# Superseal.net
KiCad netlist of a schematic drawn in Altium Designer
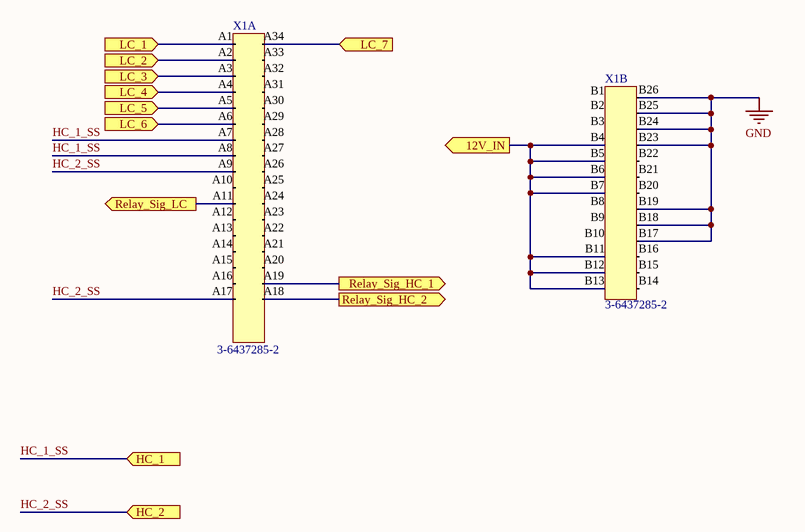
[diagram p0: Superseal.SchDoc]

(export (version "E")
  (design (tool "Eeschema 10.0.6"))
  (components
    (comp (ref "X1")
      (value "3-6437285-2")
      (footprint "SUPERSEAL 60POS 90Deg")
      (description "90 Degree")
      (libsource (lib "Altium-Lib") (part "CONN Superseal 60POS"))
    )
  )
  (nets
    (net (code "1") (name "/12V_IN") (class "Default")
      (node (ref "X1") (pin "B11") (pintype "bidirectional"))
      (node (ref "X1") (pin "B12") (pintype "bidirectional"))
      (node (ref "X1") (pin "B13") (pintype "bidirectional"))
      (node (ref "X1") (pin "B4") (pintype "bidirectional"))
      (node (ref "X1") (pin "B5") (pintype "bidirectional"))
      (node (ref "X1") (pin "B6") (pintype "bidirectional"))
      (node (ref "X1") (pin "B7") (pintype "bidirectional"))
    )
    (net (code "2") (name "/HC_1_SS") (class "Default")
      (node (ref "X1") (pin "A7") (pintype "bidirectional"))
      (node (ref "X1") (pin "A8") (pintype "bidirectional"))
    )
    (net (code "3") (name "/HC_2_SS") (class "Default")
      (node (ref "X1") (pin "A17") (pintype "bidirectional"))
      (node (ref "X1") (pin "A9") (pintype "bidirectional"))
    )
    (net (code "4") (name "/LC_1") (class "Default") (node (ref "X1") (pin "A1") (pintype "bidirectional")))
    (net (code "5") (name "/LC_2") (class "Default") (node (ref "X1") (pin "A2") (pintype "bidirectional")))
    (net (code "6") (name "/LC_3") (class "Default") (node (ref "X1") (pin "A3") (pintype "bidirectional")))
    (net (code "7") (name "/LC_4") (class "Default") (node (ref "X1") (pin "A4") (pintype "bidirectional")))
    (net (code "8") (name "/LC_5") (class "Default") (node (ref "X1") (pin "A5") (pintype "bidirectional")))
    (net (code "9") (name "/LC_6") (class "Default") (node (ref "X1") (pin "A6") (pintype "bidirectional")))
    (net (code "10") (name "/LC_7") (class "Default") (node (ref "X1") (pin "A34") (pintype "bidirectional")))
    (net (code "11") (name "/Relay_Sig_HC_1") (class "Default")
      (node (ref "X1") (pin "A19") (pintype "bidirectional"))
    )
    (net (code "12") (name "/Relay_Sig_HC_2") (class "Default")
      (node (ref "X1") (pin "A18") (pintype "bidirectional"))
    )
    (net (code "13") (name "/Relay_Sig_LC") (class "Default")
      (node (ref "X1") (pin "A11") (pintype "bidirectional"))
    )
    (net (code "14") (name "GND") (class "Default")
      (node (ref "X1") (pin "B17") (pintype "bidirectional"))
      (node (ref "X1") (pin "B18") (pintype "bidirectional"))
      (node (ref "X1") (pin "B19") (pintype "bidirectional"))
      (node (ref "X1") (pin "B23") (pintype "bidirectional"))
      (node (ref "X1") (pin "B24") (pintype "bidirectional"))
      (node (ref "X1") (pin "B25") (pintype "bidirectional"))
      (node (ref "X1") (pin "B26") (pintype "bidirectional"))
    )
    (net (code "15") (name "unconnected-(X1-PadA10)") (class "Default")
      (node (ref "X1") (pin "A10") (pintype "bidirectional"))
    )
    (net (code "16") (name "unconnected-(X1-PadA12)") (class "Default")
      (node (ref "X1") (pin "A12") (pintype "bidirectional"))
    )
    (net (code "17") (name "unconnected-(X1-PadA13)") (class "Default")
      (node (ref "X1") (pin "A13") (pintype "bidirectional"))
    )
    (net (code "18") (name "unconnected-(X1-PadA14)") (class "Default")
      (node (ref "X1") (pin "A14") (pintype "bidirectional"))
    )
    (net (code "19") (name "unconnected-(X1-PadA15)") (class "Default")
      (node (ref "X1") (pin "A15") (pintype "bidirectional"))
    )
    (net (code "20") (name "unconnected-(X1-PadA16)") (class "Default")
      (node (ref "X1") (pin "A16") (pintype "bidirectional"))
    )
    (net (code "21") (name "unconnected-(X1-PadA20)") (class "Default")
      (node (ref "X1") (pin "A20") (pintype "bidirectional"))
    )
    (net (code "22") (name "unconnected-(X1-PadA21)") (class "Default")
      (node (ref "X1") (pin "A21") (pintype "bidirectional"))
    )
    (net (code "23") (name "unconnected-(X1-PadA22)") (class "Default")
      (node (ref "X1") (pin "A22") (pintype "bidirectional"))
    )
    (net (code "24") (name "unconnected-(X1-PadA23)") (class "Default")
      (node (ref "X1") (pin "A23") (pintype "bidirectional"))
    )
    (net (code "25") (name "unconnected-(X1-PadA24)") (class "Default")
      (node (ref "X1") (pin "A24") (pintype "bidirectional"))
    )
    (net (code "26") (name "unconnected-(X1-PadA25)") (class "Default")
      (node (ref "X1") (pin "A25") (pintype "bidirectional"))
    )
    (net (code "27") (name "unconnected-(X1-PadA26)") (class "Default")
      (node (ref "X1") (pin "A26") (pintype "bidirectional"))
    )
    (net (code "28") (name "unconnected-(X1-PadA27)") (class "Default")
      (node (ref "X1") (pin "A27") (pintype "bidirectional"))
    )
    (net (code "29") (name "unconnected-(X1-PadA28)") (class "Default")
      (node (ref "X1") (pin "A28") (pintype "bidirectional"))
    )
    (net (code "30") (name "unconnected-(X1-PadA29)") (class "Default")
      (node (ref "X1") (pin "A29") (pintype "bidirectional"))
    )
    (net (code "31") (name "unconnected-(X1-PadA30)") (class "Default")
      (node (ref "X1") (pin "A30") (pintype "bidirectional"))
    )
    (net (code "32") (name "unconnected-(X1-PadA31)") (class "Default")
      (node (ref "X1") (pin "A31") (pintype "bidirectional"))
    )
    (net (code "33") (name "unconnected-(X1-PadA32)") (class "Default")
      (node (ref "X1") (pin "A32") (pintype "bidirectional"))
    )
    (net (code "34") (name "unconnected-(X1-PadA33)") (class "Default")
      (node (ref "X1") (pin "A33") (pintype "bidirectional"))
    )
    (net (code "35") (name "unconnected-(X1-PadB1)") (class "Default")
      (node (ref "X1") (pin "B1") (pintype "bidirectional"))
    )
    (net (code "36") (name "unconnected-(X1-PadB2)") (class "Default")
      (node (ref "X1") (pin "B2") (pintype "bidirectional"))
    )
    (net (code "37") (name "unconnected-(X1-PadB3)") (class "Default")
      (node (ref "X1") (pin "B3") (pintype "bidirectional"))
    )
    (net (code "38") (name "unconnected-(X1-PadB8)") (class "Default")
      (node (ref "X1") (pin "B8") (pintype "bidirectional"))
    )
    (net (code "39") (name "unconnected-(X1-PadB9)") (class "Default")
      (node (ref "X1") (pin "B9") (pintype "bidirectional"))
    )
    (net (code "40") (name "unconnected-(X1-PadB10)") (class "Default")
      (node (ref "X1") (pin "B10") (pintype "bidirectional"))
    )
    (net (code "41") (name "unconnected-(X1-PadB14)") (class "Default")
      (node (ref "X1") (pin "B14") (pintype "bidirectional"))
    )
    (net (code "42") (name "unconnected-(X1-PadB15)") (class "Default")
      (node (ref "X1") (pin "B15") (pintype "bidirectional"))
    )
    (net (code "43") (name "unconnected-(X1-PadB16)") (class "Default")
      (node (ref "X1") (pin "B16") (pintype "bidirectional"))
    )
    (net (code "44") (name "unconnected-(X1-PadB20)") (class "Default")
      (node (ref "X1") (pin "B20") (pintype "bidirectional"))
    )
    (net (code "45") (name "unconnected-(X1-PadB21)") (class "Default")
      (node (ref "X1") (pin "B21") (pintype "bidirectional"))
    )
    (net (code "46") (name "unconnected-(X1-PadB22)") (class "Default")
      (node (ref "X1") (pin "B22") (pintype "bidirectional"))
    )
  )
)
